# v0_2_0.net
KiCad netlist of a schematic drawn in EAGLE
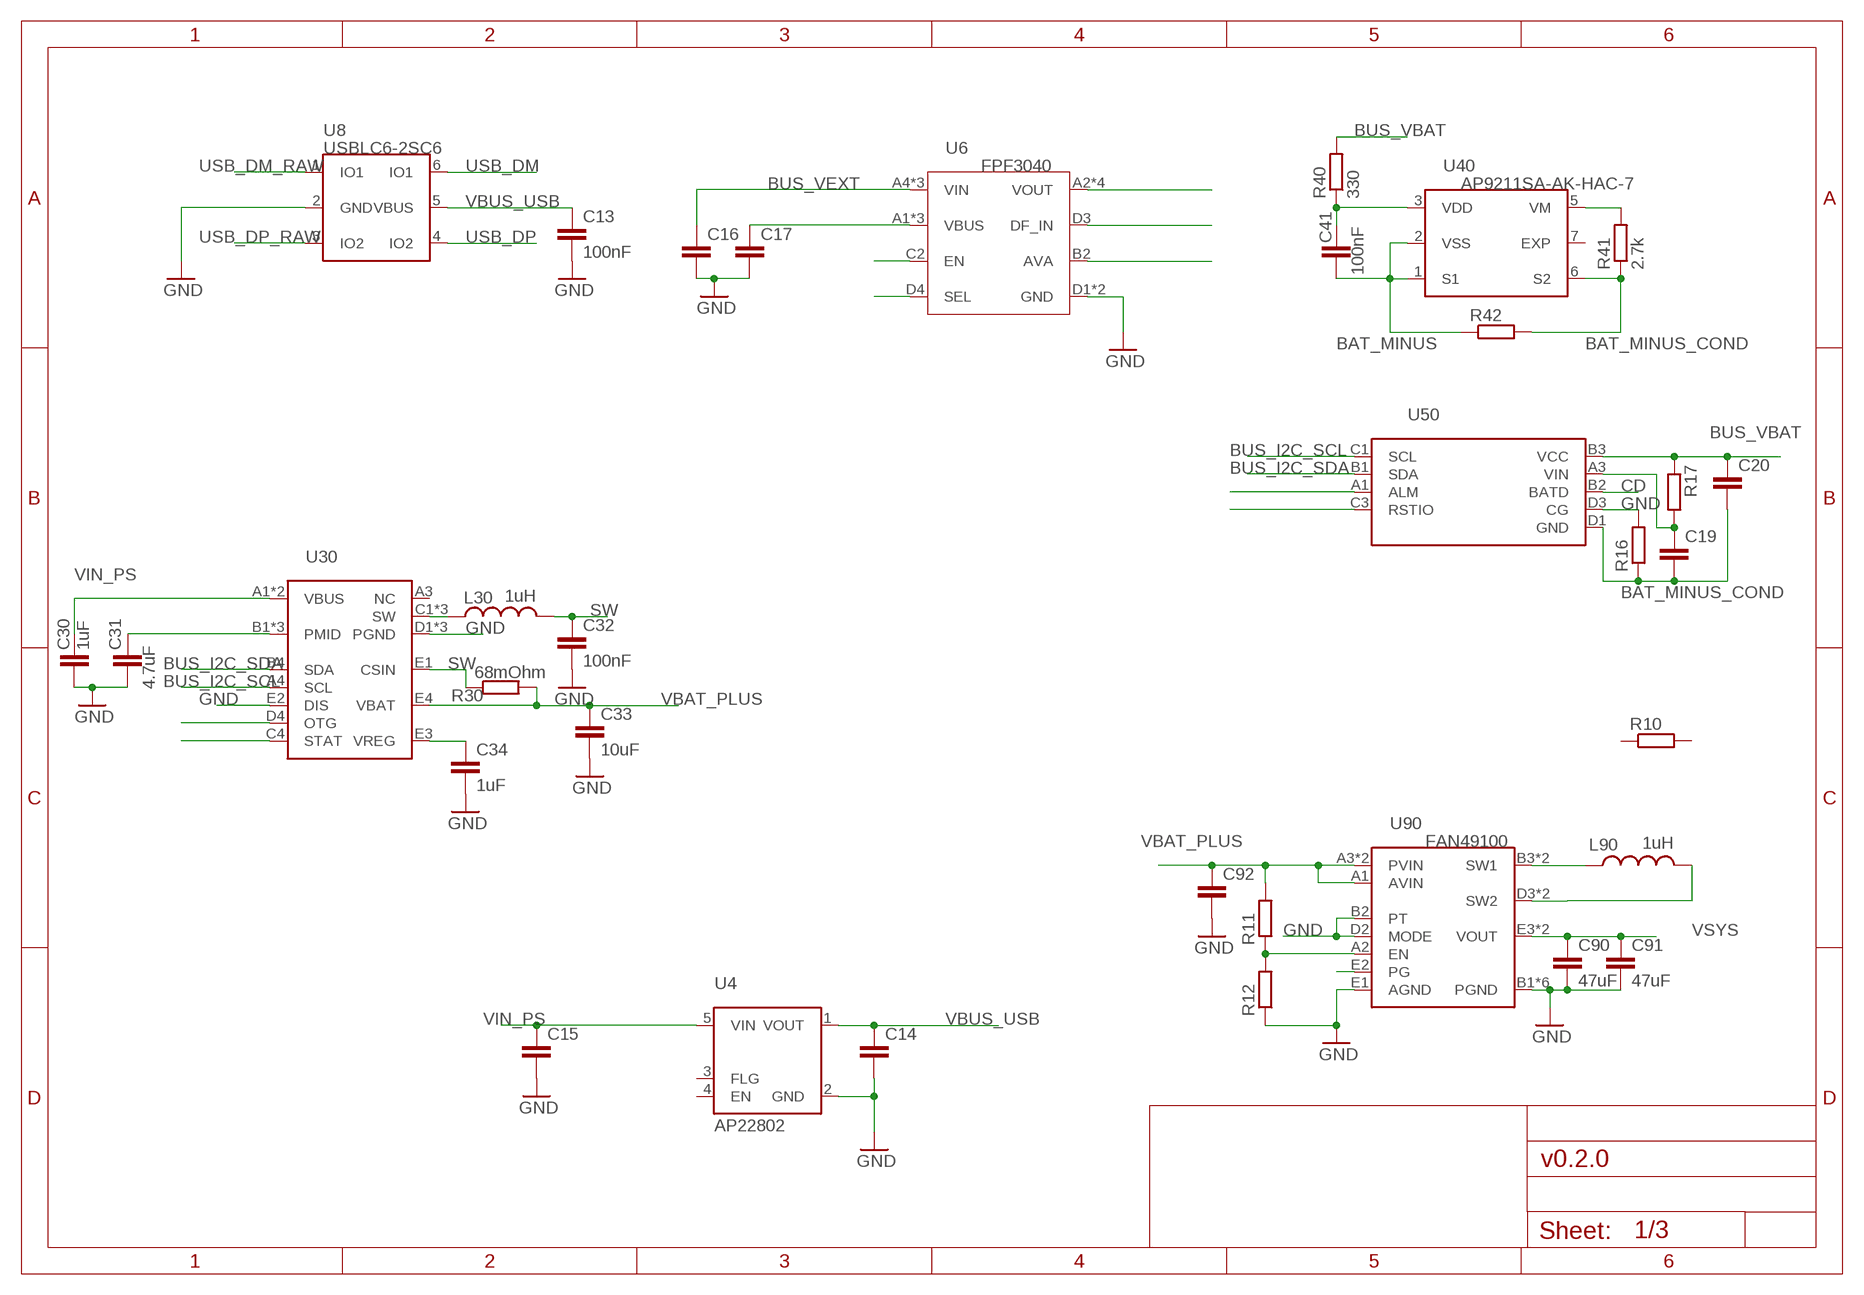
[diagram p0: schematic, sheet 1]
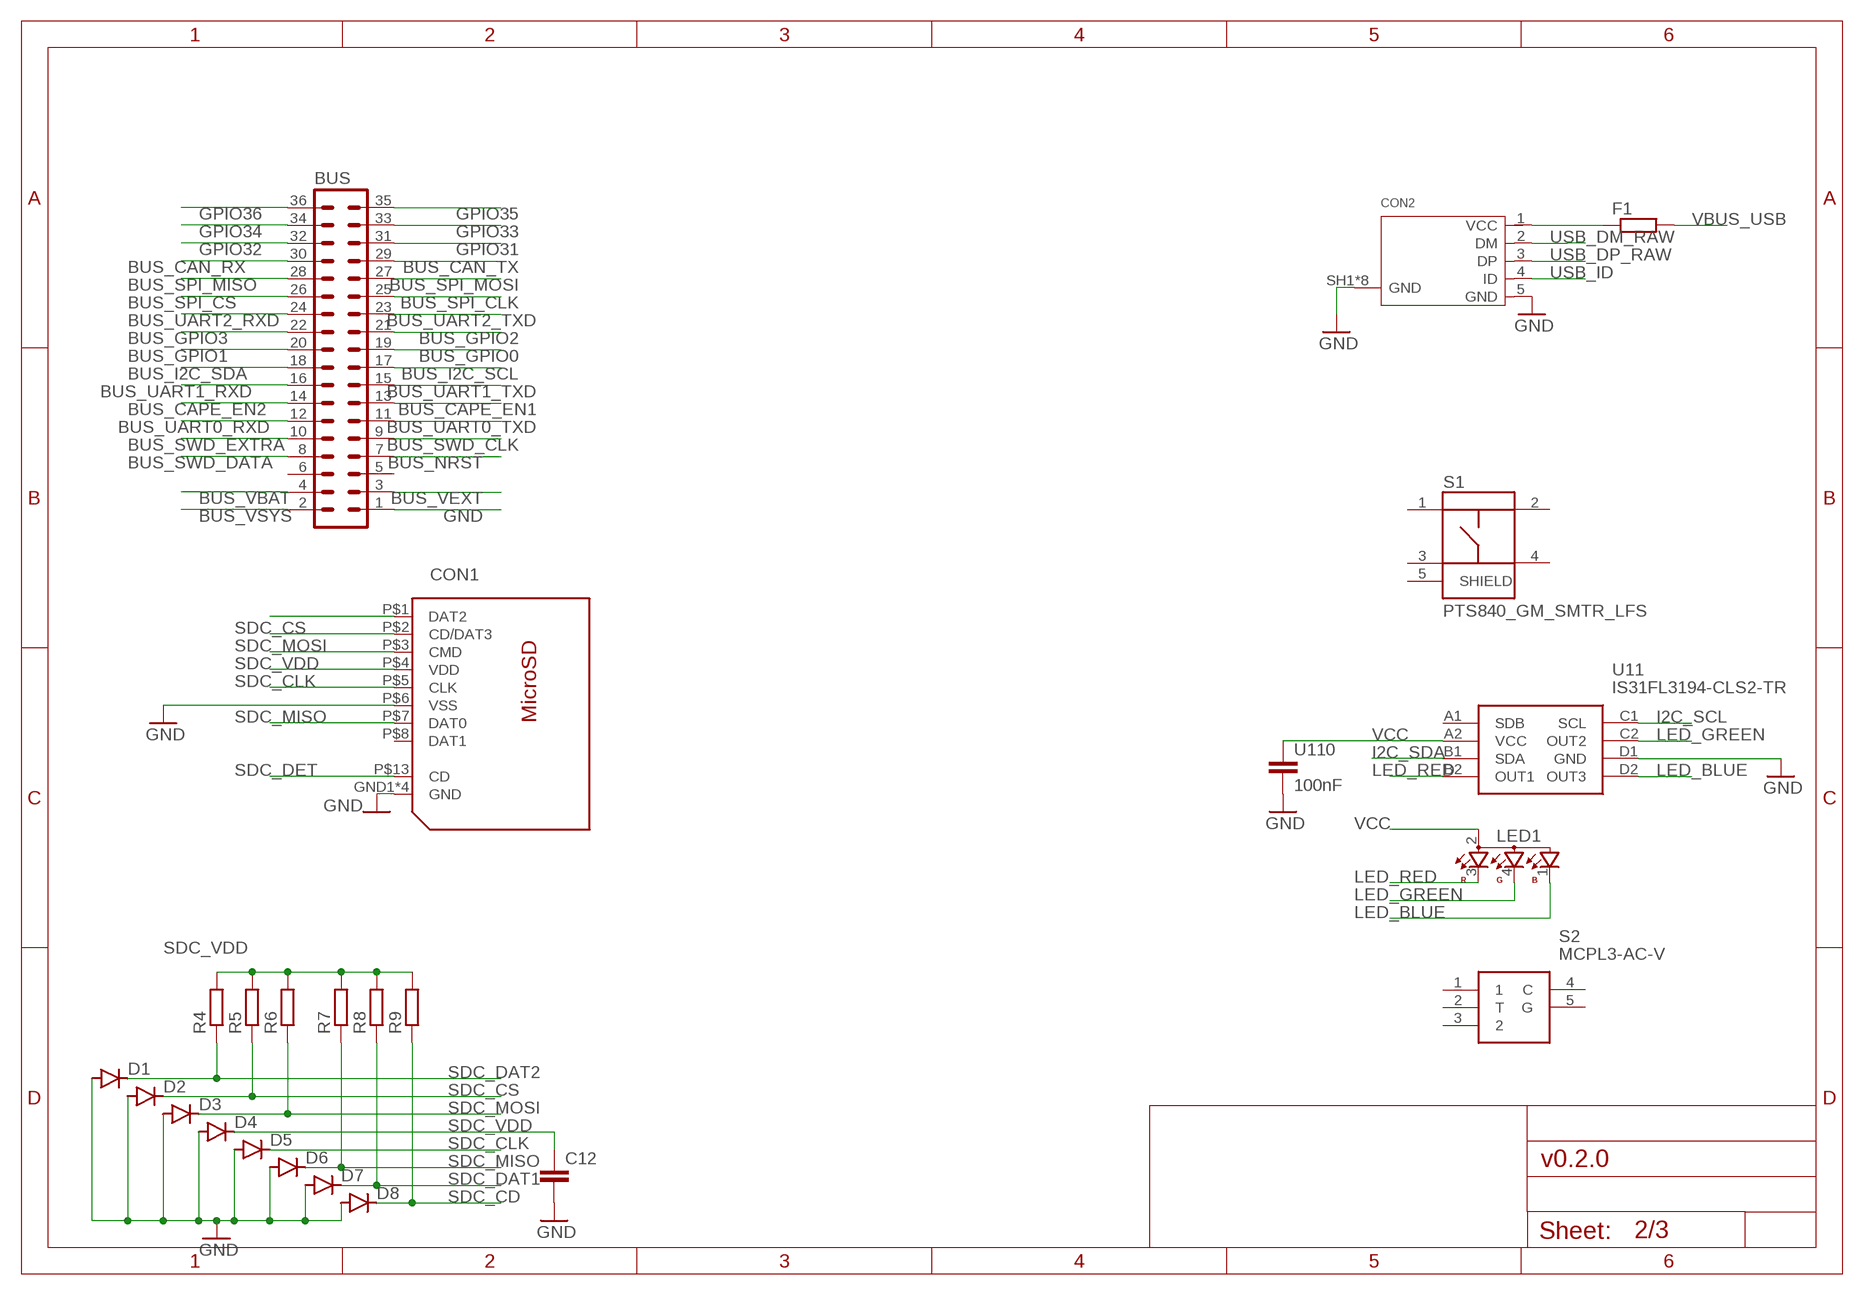
[diagram p1: schematic, sheet 2]
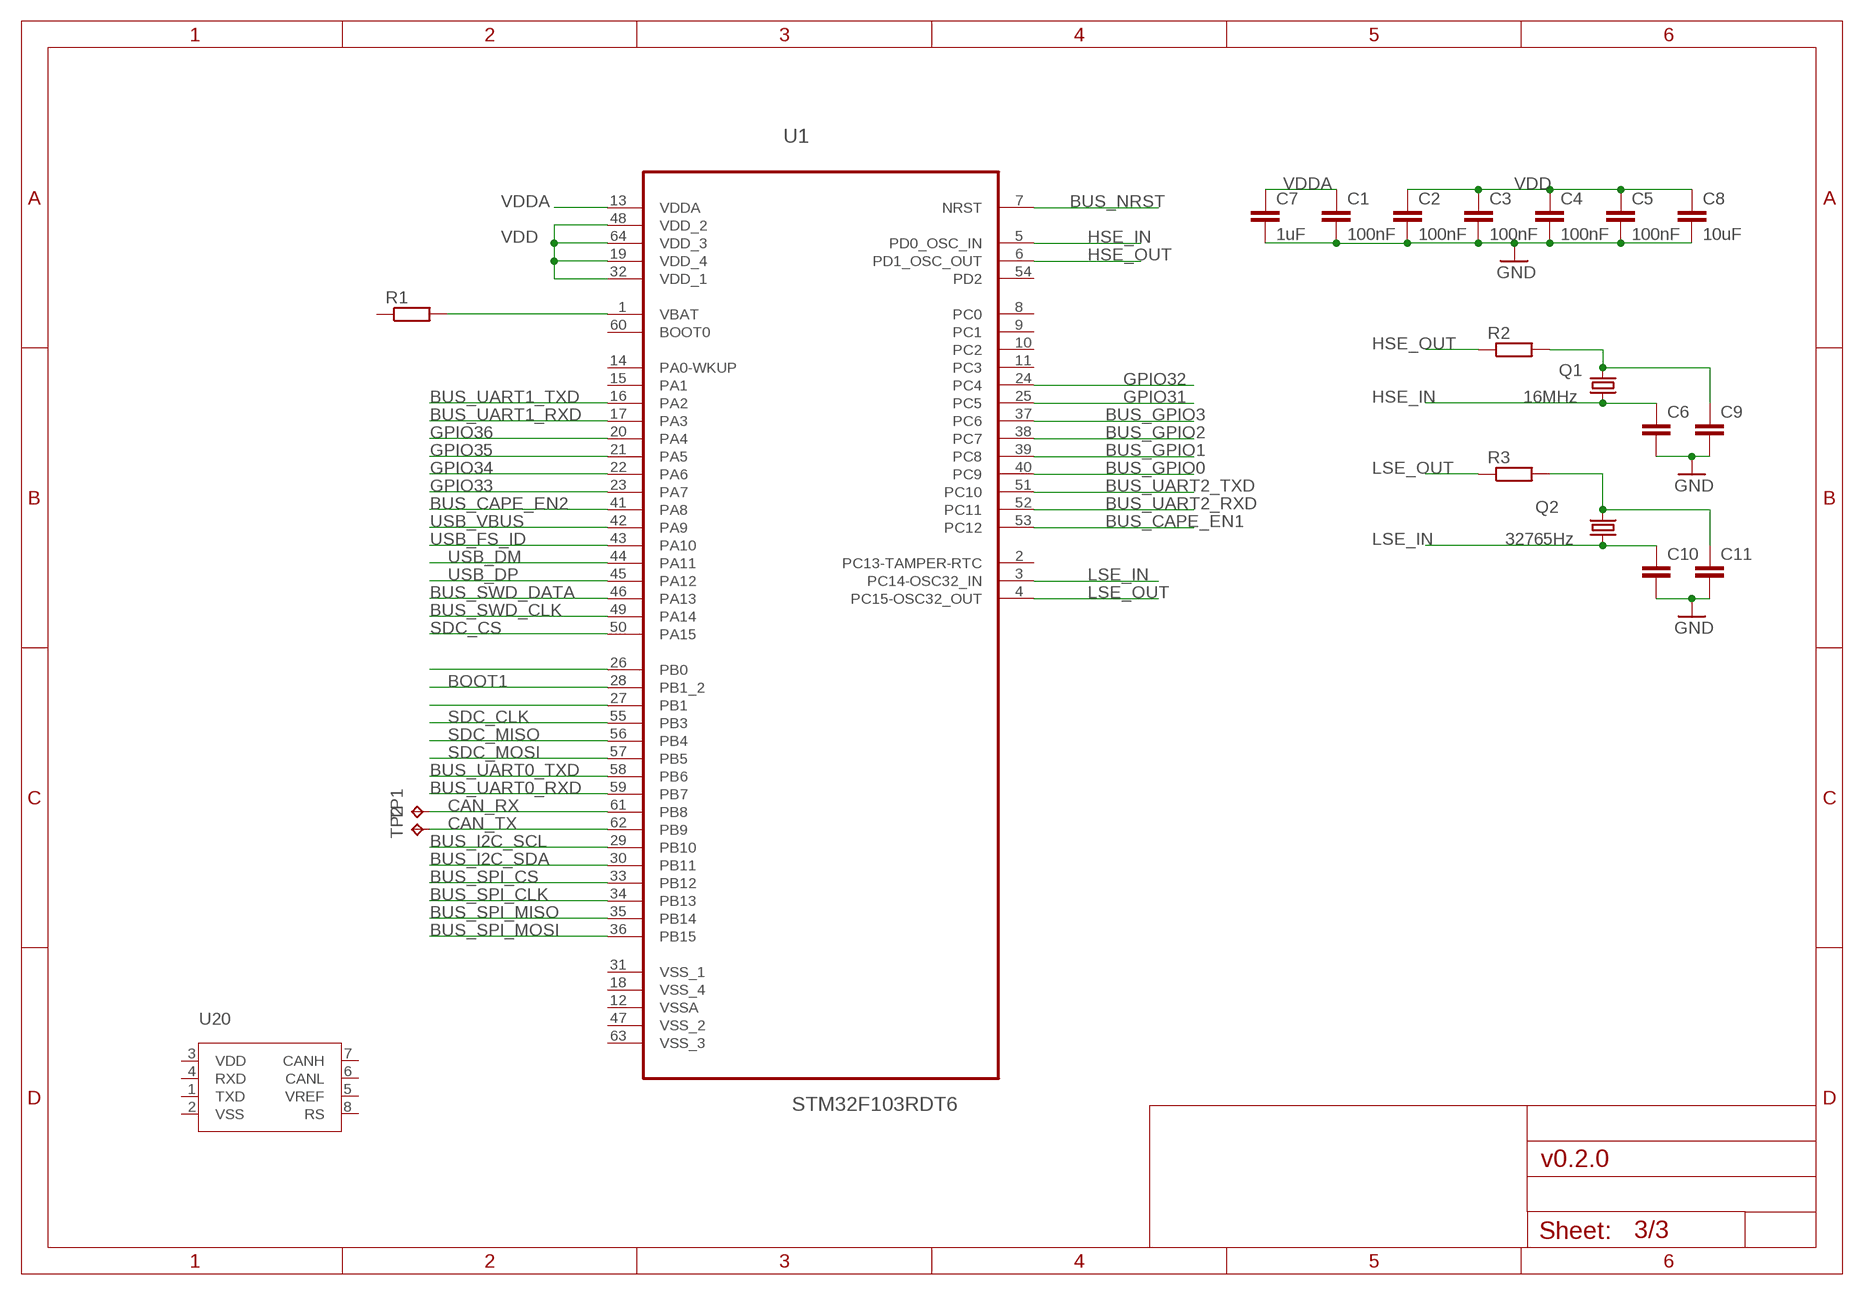
[diagram p2: schematic, sheet 3]

(export (version "E")
  (design (tool "Eeschema 10.0.6"))
  (components
    (comp (ref "C13")
      (value "100nF")
      (footprint "eagle-import:C0402")
      (libsource (lib "eagle-import") (part "C-EUC0402"))
    )
    (comp (ref "C14")
      (value "C-EUC0603")
      (footprint "eagle-import:C0603")
      (libsource (lib "eagle-import") (part "C-EUC0603"))
    )
    (comp (ref "C15")
      (value "C-EUC0603")
      (footprint "eagle-import:C0603")
      (libsource (lib "eagle-import") (part "C-EUC0603"))
    )
    (comp (ref "C16")
      (value "C-EUC0603")
      (footprint "eagle-import:C0603")
      (libsource (lib "eagle-import") (part "C-EUC0603"))
    )
    (comp (ref "C17")
      (value "C-EUC0603")
      (footprint "eagle-import:C0603")
      (libsource (lib "eagle-import") (part "C-EUC0603"))
    )
    (comp (ref "C19")
      (value "C-EUC0402")
      (footprint "eagle-import:C0402")
      (libsource (lib "eagle-import") (part "C-EUC0402"))
    )
    (comp (ref "C20")
      (value "C-EUC0402")
      (footprint "eagle-import:C0402")
      (libsource (lib "eagle-import") (part "C-EUC0402"))
    )
    (comp (ref "C30")
      (value "1uF")
      (footprint "eagle-import:C0402")
      (libsource (lib "eagle-import") (part "C-EUC0402"))
    )
    (comp (ref "C31")
      (value "4.7uF")
      (footprint "eagle-import:C0603")
      (libsource (lib "eagle-import") (part "C-EUC0603"))
    )
    (comp (ref "C32")
      (value "100nF")
      (footprint "eagle-import:C0402")
      (libsource (lib "eagle-import") (part "C-EUC0402"))
    )
    (comp (ref "C33")
      (value "10uF")
      (footprint "eagle-import:C0603")
      (libsource (lib "eagle-import") (part "C-EUC0603"))
    )
    (comp (ref "C34")
      (value "1uF")
      (footprint "eagle-import:C0402")
      (libsource (lib "eagle-import") (part "C-EUC0402"))
    )
    (comp (ref "C41")
      (value "100nF")
      (footprint "eagle-import:C0402")
      (libsource (lib "eagle-import") (part "C-EUC0402"))
    )
    (comp (ref "C90")
      (value "47uF")
      (footprint "eagle-import:C0805")
      (libsource (lib "eagle-import") (part "C-EUC0805"))
    )
    (comp (ref "C91")
      (value "47uF")
      (footprint "eagle-import:C0805")
      (libsource (lib "eagle-import") (part "C-EUC0805"))
    )
    (comp (ref "C92")
      (value "C-EUC0805")
      (footprint "eagle-import:C0805")
      (libsource (lib "eagle-import") (part "C-EUC0805"))
    )
    (comp (ref "L30")
      (value "1uH")
      (footprint "eagle-import:L3230M")
      (libsource (lib "eagle-import") (part "DJNR3015"))
    )
    (comp (ref "L90")
      (value "1uH")
      (footprint "eagle-import:L3230M")
      (libsource (lib "eagle-import") (part "DJNR3015"))
    )
    (comp (ref "R10")
      (value "R-EU_R0603")
      (footprint "eagle-import:R0603")
      (libsource (lib "eagle-import") (part "R-EU_R0603"))
    )
    (comp (ref "R11")
      (value "R-EU_R0402")
      (footprint "eagle-import:R0402")
      (libsource (lib "eagle-import") (part "R-EU_R0402"))
    )
    (comp (ref "R12")
      (value "R-EU_R0402")
      (footprint "eagle-import:R0402")
      (libsource (lib "eagle-import") (part "R-EU_R0402"))
    )
    (comp (ref "R16")
      (value "R-EU_R0805")
      (footprint "eagle-import:R0805")
      (libsource (lib "eagle-import") (part "R-EU_R0805"))
    )
    (comp (ref "R17")
      (value "R-EU_R0402")
      (footprint "eagle-import:R0402")
      (libsource (lib "eagle-import") (part "R-EU_R0402"))
    )
    (comp (ref "R30")
      (value "68mOhm")
      (footprint "eagle-import:R0805")
      (libsource (lib "eagle-import") (part "R-EU_R0805"))
    )
    (comp (ref "R40")
      (value "330")
      (footprint "eagle-import:R0402")
      (libsource (lib "eagle-import") (part "R-EU_R0402"))
    )
    (comp (ref "R41")
      (value "2.7k")
      (footprint "eagle-import:R0402")
      (libsource (lib "eagle-import") (part "R-EU_R0402"))
    )
    (comp (ref "R42")
      (value "R-EU_R0603")
      (footprint "eagle-import:R0603")
      (libsource (lib "eagle-import") (part "R-EU_R0603"))
    )
    (comp (ref "U4")
      (value "AP22802")
      (footprint "eagle-import:SOT25")
      (libsource (lib "eagle-import") (part "AP22802"))
    )
    (comp (ref "U6")
      (value "FPF3040")
      (footprint "eagle-import:BGA16C40P4X4_196X176X60")
      (libsource (lib "eagle-import") (part "FPF3040"))
    )
    (comp (ref "U8")
      (value "USBLC6-2SC6")
      (footprint "eagle-import:SOT95P280X110-6")
      (libsource (lib "eagle-import") (part "USBLC6-2SC6"))
    )
    (comp (ref "U30")
      (value "FAN54015")
      (footprint "eagle-import:BGA20C40P4X5_196X187X55")
      (libsource (lib "eagle-import") (part "FAN54015"))
    )
    (comp (ref "U40")
      (value "AP9211SA-AK-HAC-7")
      (footprint "eagle-import:DFN200X300X60-7N")
      (fields (field (name "MF") "Diodes Inc."))
      (libsource (lib "eagle-import") (part "AP9211SA-AK-HAC-7"))
    )
    (comp (ref "U50")
      (value "STC3115")
      (footprint "eagle-import:BGA12C40P4X3_137X201X65")
      (libsource (lib "eagle-import") (part "STC3115"))
    )
    (comp (ref "U90")
      (value "FAN49100")
      (footprint "eagle-import:BGA20C40P4X5_201X161X60")
      (libsource (lib "eagle-import") (part "FAN49100"))
    )
    (comp (ref "C1")
      (value "100nF")
      (footprint "eagle-import:C0402")
      (libsource (lib "eagle-import") (part "C-EUC0402"))
    )
    (comp (ref "C2")
      (value "100nF")
      (footprint "eagle-import:C0402")
      (libsource (lib "eagle-import") (part "C-EUC0402"))
    )
    (comp (ref "C3")
      (value "100nF")
      (footprint "eagle-import:C0402")
      (libsource (lib "eagle-import") (part "C-EUC0402"))
    )
    (comp (ref "C4")
      (value "100nF")
      (footprint "eagle-import:C0402")
      (libsource (lib "eagle-import") (part "C-EUC0402"))
    )
    (comp (ref "C5")
      (value "100nF")
      (footprint "eagle-import:C0402")
      (libsource (lib "eagle-import") (part "C-EUC0402"))
    )
    (comp (ref "C6")
      (value "C-EUC0402")
      (footprint "eagle-import:C0402")
      (libsource (lib "eagle-import") (part "C-EUC0402"))
    )
    (comp (ref "C7")
      (value "1uF")
      (footprint "eagle-import:C0402")
      (libsource (lib "eagle-import") (part "C-EUC0402"))
    )
    (comp (ref "C8")
      (value "10uF")
      (footprint "eagle-import:C0603")
      (libsource (lib "eagle-import") (part "C-EUC0603"))
    )
    (comp (ref "C9")
      (value "C-EUC0402")
      (footprint "eagle-import:C0402")
      (libsource (lib "eagle-import") (part "C-EUC0402"))
    )
    (comp (ref "C10")
      (value "C-EUC0402")
      (footprint "eagle-import:C0402")
      (libsource (lib "eagle-import") (part "C-EUC0402"))
    )
    (comp (ref "C11")
      (value "C-EUC0402")
      (footprint "eagle-import:C0402")
      (libsource (lib "eagle-import") (part "C-EUC0402"))
    )
    (comp (ref "Q1")
      (value "16MHz")
      (footprint "eagle-import:3.2X2.5_KX-7")
      (libsource (lib "eagle-import") (part "KX-7"))
    )
    (comp (ref "Q2")
      (value "32765Hz")
      (footprint "eagle-import:3.2X1.5")
      (libsource (lib "eagle-import") (part "KX-327-NHF"))
    )
    (comp (ref "R1")
      (value "R-EU_R0402")
      (footprint "eagle-import:R0402")
      (libsource (lib "eagle-import") (part "R-EU_R0402"))
    )
    (comp (ref "R2")
      (value "R-EU_R0402")
      (footprint "eagle-import:R0402")
      (libsource (lib "eagle-import") (part "R-EU_R0402"))
    )
    (comp (ref "R3")
      (value "R-EU_R0402")
      (footprint "eagle-import:R0402")
      (libsource (lib "eagle-import") (part "R-EU_R0402"))
    )
    (comp (ref "TP1")
      (value "TPB1,27")
      (footprint "eagle-import:B1,27")
      (libsource (lib "eagle-import") (part "TPB1,27"))
    )
    (comp (ref "TP2")
      (value "TPB1,27")
      (footprint "eagle-import:B1,27")
      (libsource (lib "eagle-import") (part "TPB1,27"))
    )
    (comp (ref "U1")
      (value "STM32F103RDT6")
      (footprint "eagle-import:QFP50P1200X1200X160-64N")
      (fields (field (name "MF") "STMicroelectronics"))
      (libsource (lib "eagle-import") (part "STM32F103RDT6"))
    )
    (comp (ref "U20")
      (value "MCP2551")
      (footprint "eagle-import:SOIC8")
      (libsource (lib "eagle-import") (part "MCP2551"))
    )
    (comp (ref "BUS")
      (value "MA18-2")
      (footprint "eagle-import:MA18-2")
      (libsource (lib "eagle-import") (part "MA18-2"))
    )
    (comp (ref "C12")
      (value "C-EUC0402")
      (footprint "eagle-import:C0402")
      (libsource (lib "eagle-import") (part "C-EUC0402"))
    )
    (comp (ref "CON1")
      (value "112J-TXAR")
      (footprint "eagle-import:112J")
      (libsource (lib "eagle-import") (part "112J-TXAR"))
    )
    (comp (ref "CON2")
      (value "10118194-0001LF")
      (footprint "eagle-import:10118194")
      (libsource (lib "eagle-import") (part "10118194-0001LF"))
    )
    (comp (ref "D1")
      (value "DIODE-SOD523")
      (footprint "eagle-import:SOD523")
      (libsource (lib "eagle-import") (part "DIODE-SOD523"))
    )
    (comp (ref "D2")
      (value "DIODE-SOD523")
      (footprint "eagle-import:SOD523")
      (libsource (lib "eagle-import") (part "DIODE-SOD523"))
    )
    (comp (ref "D3")
      (value "DIODE-SOD523")
      (footprint "eagle-import:SOD523")
      (libsource (lib "eagle-import") (part "DIODE-SOD523"))
    )
    (comp (ref "D4")
      (value "DIODE-SOD523")
      (footprint "eagle-import:SOD523")
      (libsource (lib "eagle-import") (part "DIODE-SOD523"))
    )
    (comp (ref "D5")
      (value "DIODE-SOD523")
      (footprint "eagle-import:SOD523")
      (libsource (lib "eagle-import") (part "DIODE-SOD523"))
    )
    (comp (ref "D6")
      (value "DIODE-SOD523")
      (footprint "eagle-import:SOD523")
      (libsource (lib "eagle-import") (part "DIODE-SOD523"))
    )
    (comp (ref "D7")
      (value "DIODE-SOD523")
      (footprint "eagle-import:SOD523")
      (libsource (lib "eagle-import") (part "DIODE-SOD523"))
    )
    (comp (ref "D8")
      (value "DIODE-SOD523")
      (footprint "eagle-import:SOD523")
      (libsource (lib "eagle-import") (part "DIODE-SOD523"))
    )
    (comp (ref "F1")
      (value "R-EU_R0603")
      (footprint "eagle-import:R0603")
      (libsource (lib "eagle-import") (part "R-EU_R0603"))
    )
    (comp (ref "LED1")
      (value "OSTB1204C1E")
      (footprint "eagle-import:321015RGB")
      (libsource (lib "eagle-import") (part "OSTB1204C1E"))
    )
    (comp (ref "R4")
      (value "R-EU_R0402")
      (footprint "eagle-import:R0402")
      (libsource (lib "eagle-import") (part "R-EU_R0402"))
    )
    (comp (ref "R5")
      (value "R-EU_R0402")
      (footprint "eagle-import:R0402")
      (libsource (lib "eagle-import") (part "R-EU_R0402"))
    )
    (comp (ref "R6")
      (value "R-EU_R0402")
      (footprint "eagle-import:R0402")
      (libsource (lib "eagle-import") (part "R-EU_R0402"))
    )
    (comp (ref "R7")
      (value "R-EU_R0402")
      (footprint "eagle-import:R0402")
      (libsource (lib "eagle-import") (part "R-EU_R0402"))
    )
    (comp (ref "R8")
      (value "R-EU_R0402")
      (footprint "eagle-import:R0402")
      (libsource (lib "eagle-import") (part "R-EU_R0402"))
    )
    (comp (ref "R9")
      (value "R-EU_R0402")
      (footprint "eagle-import:R0402")
      (libsource (lib "eagle-import") (part "R-EU_R0402"))
    )
    (comp (ref "S1")
      (value "PTS840_GM_SMTR_LFS")
      (footprint "eagle-import:SW_PTS840GMSMTRLFS")
      (fields (field (name "MF") "C&K") (field (name "MP") "PTS840 GM SMTR LFS"))
      (libsource (lib "eagle-import") (part "PTS840_GM_SMTR_LFS"))
    )
    (comp (ref "S2")
      (value "MCPL3-AC-V")
      (footprint "eagle-import:MCPL3-AC-V")
      (libsource (lib "eagle-import") (part "MCPL3-AC-V"))
    )
    (comp (ref "U11")
      (value "IS31FL3194-CLS2-TR")
      (footprint "eagle-import:BGA8C40P2X4_99X159X42")
      (fields (field (name "MOUSER_PART_NUMBER") "870-IS31FL3194CLS2TR"))
      (libsource (lib "eagle-import") (part "IS31FL3194-CLS2-TR"))
    )
    (comp (ref "U110")
      (value "100nF")
      (footprint "eagle-import:C0402")
      (libsource (lib "eagle-import") (part "C-EUC0402"))
    )
  )
  (nets
    (net (code "1") (name "BAT_MINUS") (class "Default")
      (node (ref "C41") (pin "2") (pinfunction "2_2") (pintype "passive"))
      (node (ref "R42") (pin "1") (pinfunction "1_1") (pintype "passive"))
      (node (ref "U40") (pin "1") (pinfunction "S1_1") (pintype "output"))
      (node (ref "U40") (pin "2") (pinfunction "VSS_2") (pintype "power_in"))
    )
    (net (code "2") (name "BAT_MINUS_COND") (class "Default")
      (node (ref "C19") (pin "2") (pinfunction "2_2") (pintype "passive"))
      (node (ref "C20") (pin "2") (pinfunction "2_2") (pintype "passive"))
      (node (ref "R16") (pin "1") (pinfunction "1_1") (pintype "passive"))
      (node (ref "R41") (pin "1") (pinfunction "1_1") (pintype "passive"))
      (node (ref "R42") (pin "2") (pinfunction "2_2") (pintype "passive"))
      (node (ref "U40") (pin "6") (pinfunction "S2_6") (pintype "output"))
      (node (ref "U50") (pin "D1") (pinfunction "GND_D1") (pintype "bidirectional"))
    )
    (net (code "3") (name "BOOT1") (class "Default")
      (node (ref "U1") (pin "28") (pinfunction "PB1_2_28") (pintype "bidirectional"))
    )
    (net (code "4") (name "BUS_CAN_RX") (class "Default")
      (node (ref "BUS") (pin "30") (pinfunction "30_30") (pintype "passive"))
    )
    (net (code "5") (name "BUS_CAN_TX") (class "Default")
      (node (ref "BUS") (pin "29") (pinfunction "29_29") (pintype "passive"))
    )
    (net (code "6") (name "BUS_CAPE_EN1") (class "Default")
      (node (ref "BUS") (pin "13") (pinfunction "13_13") (pintype "passive"))
      (node (ref "U1") (pin "53") (pinfunction "PC12_53") (pintype "bidirectional"))
    )
    (net (code "7") (name "BUS_CAPE_EN2") (class "Default")
      (node (ref "BUS") (pin "14") (pinfunction "14_14") (pintype "passive"))
      (node (ref "U1") (pin "41") (pinfunction "PA8_41") (pintype "bidirectional"))
    )
    (net (code "8") (name "BUS_GPIO0") (class "Default")
      (node (ref "BUS") (pin "19") (pinfunction "19_19") (pintype "passive"))
      (node (ref "U1") (pin "40") (pinfunction "PC9_40") (pintype "bidirectional"))
    )
    (net (code "9") (name "BUS_GPIO1") (class "Default")
      (node (ref "BUS") (pin "20") (pinfunction "20_20") (pintype "passive"))
      (node (ref "U1") (pin "39") (pinfunction "PC8_39") (pintype "bidirectional"))
    )
    (net (code "10") (name "BUS_GPIO2") (class "Default")
      (node (ref "BUS") (pin "21") (pinfunction "21_21") (pintype "passive"))
      (node (ref "U1") (pin "38") (pinfunction "PC7_38") (pintype "bidirectional"))
    )
    (net (code "11") (name "BUS_GPIO3") (class "Default")
      (node (ref "BUS") (pin "22") (pinfunction "22_22") (pintype "passive"))
      (node (ref "U1") (pin "37") (pinfunction "PC6_37") (pintype "bidirectional"))
    )
    (net (code "12") (name "BUS_I2C_SCL") (class "Default")
      (node (ref "BUS") (pin "17") (pinfunction "17_17") (pintype "passive"))
      (node (ref "U1") (pin "29") (pinfunction "PB10_29") (pintype "bidirectional"))
      (node (ref "U30") (pin "A4") (pinfunction "SCL_A4") (pintype "bidirectional"))
      (node (ref "U50") (pin "C1") (pinfunction "SCL_C1") (pintype "bidirectional"))
    )
    (net (code "13") (name "BUS_I2C_SDA") (class "Default")
      (node (ref "BUS") (pin "18") (pinfunction "18_18") (pintype "passive"))
      (node (ref "U1") (pin "30") (pinfunction "PB11_30") (pintype "bidirectional"))
      (node (ref "U30") (pin "B4") (pinfunction "SDA_B4") (pintype "bidirectional"))
      (node (ref "U50") (pin "B1") (pinfunction "SDA_B1") (pintype "bidirectional"))
    )
    (net (code "14") (name "BUS_NRST") (class "Default")
      (node (ref "BUS") (pin "7") (pinfunction "7_7") (pintype "passive"))
      (node (ref "U1") (pin "7") (pinfunction "NRST_7") (pintype "output"))
    )
    (net (code "15") (name "BUS_SPI_CLK") (class "Default")
      (node (ref "BUS") (pin "25") (pinfunction "25_25") (pintype "passive"))
      (node (ref "U1") (pin "34") (pinfunction "PB13_34") (pintype "bidirectional"))
    )
    (net (code "16") (name "BUS_SPI_CS") (class "Default")
      (node (ref "BUS") (pin "26") (pinfunction "26_26") (pintype "passive"))
      (node (ref "U1") (pin "33") (pinfunction "PB12_33") (pintype "bidirectional"))
    )
    (net (code "17") (name "BUS_SPI_MISO") (class "Default")
      (node (ref "BUS") (pin "28") (pinfunction "28_28") (pintype "passive"))
      (node (ref "U1") (pin "35") (pinfunction "PB14_35") (pintype "bidirectional"))
    )
    (net (code "18") (name "BUS_SPI_MOSI") (class "Default")
      (node (ref "BUS") (pin "27") (pinfunction "27_27") (pintype "passive"))
      (node (ref "U1") (pin "36") (pinfunction "PB15_36") (pintype "bidirectional"))
    )
    (net (code "19") (name "BUS_SWD_CLK") (class "Default")
      (node (ref "BUS") (pin "9") (pinfunction "9_9") (pintype "passive"))
      (node (ref "U1") (pin "49") (pinfunction "PA14_49") (pintype "bidirectional"))
    )
    (net (code "20") (name "BUS_SWD_DATA") (class "Default")
      (node (ref "BUS") (pin "8") (pinfunction "8_8") (pintype "passive"))
      (node (ref "U1") (pin "46") (pinfunction "PA13_46") (pintype "bidirectional"))
    )
    (net (code "21") (name "BUS_SWD_EXTRA") (class "Default")
      (node (ref "BUS") (pin "10") (pinfunction "10_10") (pintype "passive"))
    )
    (net (code "22") (name "BUS_UART0_RXD") (class "Default")
      (node (ref "BUS") (pin "12") (pinfunction "12_12") (pintype "passive"))
      (node (ref "U1") (pin "59") (pinfunction "PB7_59") (pintype "power_in"))
    )
    (net (code "23") (name "BUS_UART0_TXD") (class "Default")
      (node (ref "BUS") (pin "11") (pinfunction "11_11") (pintype "passive"))
      (node (ref "U1") (pin "58") (pinfunction "PB6_58") (pintype "bidirectional"))
    )
    (net (code "24") (name "BUS_UART1_RXD") (class "Default")
      (node (ref "BUS") (pin "16") (pinfunction "16_16") (pintype "passive"))
      (node (ref "U1") (pin "17") (pinfunction "PA3_17") (pintype "bidirectional"))
    )
    (net (code "25") (name "BUS_UART1_TXD") (class "Default")
      (node (ref "BUS") (pin "15") (pinfunction "15_15") (pintype "passive"))
      (node (ref "U1") (pin "16") (pinfunction "PA2_16") (pintype "bidirectional"))
    )
    (net (code "26") (name "BUS_UART2_RXD") (class "Default")
      (node (ref "BUS") (pin "24") (pinfunction "24_24") (pintype "passive"))
      (node (ref "U1") (pin "52") (pinfunction "PC11_52") (pintype "bidirectional"))
    )
    (net (code "27") (name "BUS_UART2_TXD") (class "Default")
      (node (ref "BUS") (pin "23") (pinfunction "23_23") (pintype "passive"))
      (node (ref "U1") (pin "51") (pinfunction "PC10_51") (pintype "bidirectional"))
    )
    (net (code "28") (name "BUS_VBAT") (class "Default")
      (node (ref "BUS") (pin "4") (pinfunction "4_4") (pintype "passive"))
      (node (ref "C20") (pin "1") (pinfunction "1_1") (pintype "passive"))
      (node (ref "R17") (pin "1") (pinfunction "1_1") (pintype "passive"))
      (node (ref "R40") (pin "2") (pinfunction "2_2") (pintype "passive"))
      (node (ref "U50") (pin "B3") (pinfunction "VCC_B3") (pintype "bidirectional"))
    )
    (net (code "29") (name "BUS_VEXT") (class "Default")
      (node (ref "BUS") (pin "3") (pinfunction "3_3") (pintype "passive"))
      (node (ref "C16") (pin "1") (pinfunction "1_1") (pintype "passive"))
      (node (ref "U6") (pin "A4") (pinfunction "VIN_A4") (pintype "bidirectional"))
      (node (ref "U6") (pin "B4") (pinfunction "VIN_B4") (pintype "bidirectional"))
      (node (ref "U6") (pin "C4") (pinfunction "VIN_C4") (pintype "bidirectional"))
    )
    (net (code "30") (name "BUS_VSYS") (class "Default")
      (node (ref "BUS") (pin "2") (pinfunction "2_2") (pintype "passive"))
    )
    (net (code "31") (name "CAN_RX") (class "Default")
      (node (ref "TP1") (pin "TP") (pinfunction "TP_TP") (pintype "input"))
      (node (ref "U1") (pin "61") (pinfunction "PB8_61") (pintype "bidirectional"))
    )
    (net (code "32") (name "CAN_TX") (class "Default")
      (node (ref "TP2") (pin "TP") (pinfunction "TP_TP") (pintype "input"))
      (node (ref "U1") (pin "62") (pinfunction "PB9_62") (pintype "bidirectional"))
    )
    (net (code "33") (name "CD") (class "Default")
      (node (ref "U50") (pin "B2") (pinfunction "BATD_B2") (pintype "bidirectional"))
    )
    (net (code "34") (name "DAT1") (class "Default")
      (node (ref "CON1") (pin "P$8") (pinfunction "DAT1_P$8") (pintype "power_in"))
    )
    (net (code "35") (name "EXP") (class "Default")
      (node (ref "U40") (pin "7") (pinfunction "EXP_7") (pintype "power_in"))
    )
    (net (code "36") (name "GND") (class "Default")
      (node (ref "BUS") (pin "1") (pinfunction "1_1") (pintype "passive"))
      (node (ref "C1") (pin "2") (pinfunction "2_2") (pintype "passive"))
      (node (ref "C10") (pin "2") (pinfunction "2_2") (pintype "passive"))
      (node (ref "C11") (pin "2") (pinfunction "2_2") (pintype "passive"))
      (node (ref "C12") (pin "2") (pinfunction "2_2") (pintype "passive"))
      (node (ref "C13") (pin "2") (pinfunction "2_2") (pintype "passive"))
      (node (ref "C14") (pin "2") (pinfunction "2_2") (pintype "passive"))
      (node (ref "C15") (pin "2") (pinfunction "2_2") (pintype "passive"))
      (node (ref "C16") (pin "2") (pinfunction "2_2") (pintype "passive"))
      (node (ref "C17") (pin "2") (pinfunction "2_2") (pintype "passive"))
      (node (ref "C2") (pin "2") (pinfunction "2_2") (pintype "passive"))
      (node (ref "C3") (pin "2") (pinfunction "2_2") (pintype "passive"))
      (node (ref "C30") (pin "2") (pinfunction "2_2") (pintype "passive"))
      (node (ref "C31") (pin "2") (pinfunction "2_2") (pintype "passive"))
      (node (ref "C32") (pin "2") (pinfunction "2_2") (pintype "passive"))
      (node (ref "C33") (pin "2") (pinfunction "2_2") (pintype "passive"))
      (node (ref "C34") (pin "2") (pinfunction "2_2") (pintype "passive"))
      (node (ref "C4") (pin "2") (pinfunction "2_2") (pintype "passive"))
      (node (ref "C5") (pin "2") (pinfunction "2_2") (pintype "passive"))
      (node (ref "C6") (pin "2") (pinfunction "2_2") (pintype "passive"))
      (node (ref "C7") (pin "2") (pinfunction "2_2") (pintype "passive"))
      (node (ref "C8") (pin "2") (pinfunction "2_2") (pintype "passive"))
      (node (ref "C9") (pin "2") (pinfunction "2_2") (pintype "passive"))
      (node (ref "C90") (pin "2") (pinfunction "2_2") (pintype "passive"))
      (node (ref "C91") (pin "2") (pinfunction "2_2") (pintype "passive"))
      (node (ref "C92") (pin "2") (pinfunction "2_2") (pintype "passive"))
      (node (ref "CON1") (pin "GND1") (pinfunction "GND_GND1") (pintype "power_in"))
      (node (ref "CON1") (pin "GND2") (pinfunction "GND_GND2") (pintype "power_in"))
      (node (ref "CON1") (pin "GND3") (pinfunction "GND_GND3") (pintype "power_in"))
      (node (ref "CON1") (pin "GND4") (pinfunction "GND_GND4") (pintype "power_in"))
      (node (ref "CON1") (pin "P$6") (pinfunction "VSS_P$6") (pintype "bidirectional"))
      (node (ref "CON2") (pin "5") (pinfunction "GND_5") (pintype "bidirectional"))
      (node (ref "CON2") (pin "SH1") (pinfunction "GND_SH1") (pintype "bidirectional"))
      (node (ref "CON2") (pin "SH2") (pinfunction "GND_SH2") (pintype "bidirectional"))
      (node (ref "CON2") (pin "SH3") (pinfunction "GND_SH3") (pintype "bidirectional"))
      (node (ref "CON2") (pin "SH4") (pinfunction "GND_SH4") (pintype "bidirectional"))
      (node (ref "CON2") (pin "SH5") (pinfunction "GND_SH5") (pintype "bidirectional"))
      (node (ref "CON2") (pin "SH6") (pinfunction "GND_SH6") (pintype "bidirectional"))
      (node (ref "CON2") (pin "SH7") (pinfunction "GND_SH7") (pintype "bidirectional"))
      (node (ref "CON2") (pin "SH8") (pinfunction "GND_SH8") (pintype "bidirectional"))
      (node (ref "D1") (pin "A") (pinfunction "A_A") (pintype "passive"))
      (node (ref "D2") (pin "A") (pinfunction "A_A") (pintype "passive"))
      (node (ref "D3") (pin "A") (pinfunction "A_A") (pintype "passive"))
      (node (ref "D4") (pin "A") (pinfunction "A_A") (pintype "passive"))
      (node (ref "D5") (pin "A") (pinfunction "A_A") (pintype "passive"))
      (node (ref "D6") (pin "A") (pinfunction "A_A") (pintype "passive"))
      (node (ref "D7") (pin "A") (pinfunction "A_A") (pintype "passive"))
      (node (ref "D8") (pin "A") (pinfunction "A_A") (pintype "passive"))
      (node (ref "R12") (pin "1") (pinfunction "1_1") (pintype "passive"))
      (node (ref "R16") (pin "2") (pinfunction "2_2") (pintype "passive"))
      (node (ref "U11") (pin "D1") (pinfunction "GND_D1") (pintype "bidirectional"))
      (node (ref "U110") (pin "2") (pinfunction "2_2") (pintype "passive"))
      (node (ref "U30") (pin "D1") (pinfunction "PGND_D1") (pintype "bidirectional"))
      (node (ref "U30") (pin "D2") (pinfunction "PGND_D2") (pintype "bidirectional"))
      (node (ref "U30") (pin "D3") (pinfunction "PGND_D3") (pintype "bidirectional"))
      (node (ref "U30") (pin "E2") (pinfunction "DIS_E2") (pintype "bidirectional"))
      (node (ref "U4") (pin "2") (pinfunction "GND_2") (pintype "bidirectional"))
      (node (ref "U50") (pin "D3") (pinfunction "CG_D3") (pintype "bidirectional"))
      (node (ref "U6") (pin "D1") (pinfunction "GND_D1") (pintype "bidirectional"))
      (node (ref "U6") (pin "D2") (pinfunction "GND_D2") (pintype "bidirectional"))
      (node (ref "U8") (pin "2") (pinfunction "GND_2") (pintype "bidirectional"))
      (node (ref "U90") (pin "B1") (pinfunction "PGND_B1") (pintype "bidirectional"))
      (node (ref "U90") (pin "B2") (pinfunction "PT_B2") (pintype "bidirectional"))
      (node (ref "U90") (pin "C1") (pinfunction "PGND_C1") (pintype "bidirectional"))
      (node (ref "U90") (pin "C2") (pinfunction "PGND_C2") (pintype "bidirectional"))
      (node (ref "U90") (pin "C3") (pinfunction "PGND_C3") (pintype "bidirectional"))
      (node (ref "U90") (pin "C4") (pinfunction "PGND_C4") (pintype "bidirectional"))
      (node (ref "U90") (pin "D1") (pinfunction "PGND_D1") (pintype "bidirectional"))
      (node (ref "U90") (pin "D2") (pinfunction "MODE_D2") (pintype "bidirectional"))
      (node (ref "U90") (pin "E1") (pinfunction "AGND_E1") (pintype "bidirectional"))
    )
    (net (code "37") (name "GPIO31") (class "Default")
      (node (ref "BUS") (pin "31") (pinfunction "31_31") (pintype "passive"))
      (node (ref "U1") (pin "25") (pinfunction "PC5_25") (pintype "bidirectional"))
    )
    (net (code "38") (name "GPIO32") (class "Default")
      (node (ref "BUS") (pin "32") (pinfunction "32_32") (pintype "passive"))
      (node (ref "U1") (pin "24") (pinfunction "PC4_24") (pintype "passive"))
    )
    (net (code "39") (name "GPIO33") (class "Default")
      (node (ref "BUS") (pin "33") (pinfunction "33_33") (pintype "passive"))
      (node (ref "U1") (pin "23") (pinfunction "PA7_23") (pintype "power_in"))
    )
    (net (code "40") (name "GPIO34") (class "Default")
      (node (ref "BUS") (pin "34") (pinfunction "34_34") (pintype "passive"))
      (node (ref "U1") (pin "22") (pinfunction "PA6_22") (pintype "bidirectional"))
    )
    (net (code "41") (name "GPIO35") (class "Default")
      (node (ref "BUS") (pin "35") (pinfunction "35_35") (pintype "passive"))
      (node (ref "U1") (pin "21") (pinfunction "PA5_21") (pintype "bidirectional"))
    )
    (net (code "42") (name "GPIO36") (class "Default")
      (node (ref "BUS") (pin "36") (pinfunction "36_36") (pintype "passive"))
      (node (ref "U1") (pin "20") (pinfunction "PA4_20") (pintype "bidirectional"))
    )
    (net (code "43") (name "HSE_IN") (class "Default")
      (node (ref "C6") (pin "1") (pinfunction "1_1") (pintype "passive"))
      (node (ref "Q1") (pin "1") (pinfunction "1_1") (pintype "passive"))
      (node (ref "U1") (pin "5") (pinfunction "PD0_OSC_IN_5") (pintype "input"))
    )
    (net (code "44") (name "HSE_OUT") (class "Default")
      (node (ref "R2") (pin "1") (pinfunction "1_1") (pintype "passive"))
      (node (ref "U1") (pin "6") (pinfunction "PD1_OSC_OUT_6") (pintype "output"))
    )
    (net (code "45") (name "I2C_SCL") (class "Default")
      (node (ref "U11") (pin "C1") (pinfunction "SCL_C1") (pintype "bidirectional"))
    )
    (net (code "46") (name "I2C_SDA") (class "Default")
      (node (ref "U11") (pin "B1") (pinfunction "SDA_B1") (pintype "bidirectional"))
    )
    (net (code "47") (name "LED_BLUE") (class "Default")
      (node (ref "LED1") (pin "1") (pinfunction "1_1") (pintype "passive"))
      (node (ref "U11") (pin "D2") (pinfunction "OUT3_D2") (pintype "bidirectional"))
    )
    (net (code "48") (name "LED_GREEN") (class "Default")
      (node (ref "LED1") (pin "4") (pinfunction "4_4") (pintype "passive"))
      (node (ref "U11") (pin "C2") (pinfunction "OUT2_C2") (pintype "bidirectional"))
    )
    (net (code "49") (name "LED_RED") (class "Default")
      (node (ref "LED1") (pin "3") (pinfunction "3_3") (pintype "passive"))
      (node (ref "U11") (pin "B2") (pinfunction "OUT1_B2") (pintype "bidirectional"))
    )
    (net (code "50") (name "LSE_IN") (class "Default")
      (node (ref "C10") (pin "1") (pinfunction "1_1") (pintype "passive"))
      (node (ref "Q2") (pin "1") (pinfunction "1_1") (pintype "passive"))
      (node (ref "U1") (pin "3") (pinfunction "PC14-OSC32_IN_3") (pintype "input"))
    )
    (net (code "51") (name "LSE_OUT") (class "Default")
      (node (ref "R3") (pin "1") (pinfunction "1_1") (pintype "passive"))
      (node (ref "U1") (pin "4") (pinfunction "PC15-OSC32_OUT_4") (pintype "output"))
    )
    (net (code "52") (name "Net-(C11-Pad1)") (class "Default")
      (node (ref "C11") (pin "1") (pinfunction "1_1") (pintype "passive"))
      (node (ref "Q2") (pin "2") (pinfunction "2_2") (pintype "passive"))
      (node (ref "R3") (pin "2") (pinfunction "2_2") (pintype "passive"))
    )
    (net (code "53") (name "Net-(C17-Pad1)") (class "Default")
      (node (ref "C17") (pin "1") (pinfunction "1_1") (pintype "passive"))
      (node (ref "U6") (pin "A1") (pinfunction "VBUS_A1") (pintype "bidirectional"))
      (node (ref "U6") (pin "B1") (pinfunction "VBUS_B1") (pintype "bidirectional"))
      (node (ref "U6") (pin "C1") (pinfunction "VBUS_C1") (pintype "bidirectional"))
    )
    (net (code "54") (name "Net-(C31-Pad1)") (class "Default")
      (node (ref "C31") (pin "1") (pinfunction "1_1") (pintype "passive"))
      (node (ref "U30") (pin "B1") (pinfunction "PMID_B1") (pintype "bidirectional"))
      (node (ref "U30") (pin "B2") (pinfunction "PMID_B2") (pintype "bidirectional"))
      (node (ref "U30") (pin "B3") (pinfunction "PMID_B3") (pintype "bidirectional"))
    )
    (net (code "55") (name "Net-(CON2-VCC)") (class "Default")
      (node (ref "CON2") (pin "1") (pinfunction "VCC_1") (pintype "bidirectional"))
      (node (ref "F1") (pin "1") (pinfunction "1_1") (pintype "passive"))
    )
    (net (code "56") (name "Net-(L30-Pad1)") (class "Default")
      (node (ref "L30") (pin "1") (pinfunction "1_1") (pintype "passive"))
      (node (ref "U30") (pin "C1") (pinfunction "SW_C1") (pintype "bidirectional"))
      (node (ref "U30") (pin "C2") (pinfunction "SW_C2") (pintype "bidirectional"))
      (node (ref "U30") (pin "C3") (pinfunction "SW_C3") (pintype "bidirectional"))
    )
    (net (code "57") (name "Net-(L90-Pad1)") (class "Default")
      (node (ref "L90") (pin "1") (pinfunction "1_1") (pintype "passive"))
      (node (ref "U90") (pin "B3") (pinfunction "SW1_B3") (pintype "bidirectional"))
      (node (ref "U90") (pin "B4") (pinfunction "SW1_B4") (pintype "bidirectional"))
    )
    (net (code "58") (name "Net-(L90-Pad2)") (class "Default")
      (node (ref "L90") (pin "2") (pinfunction "2_2") (pintype "passive"))
      (node (ref "U90") (pin "D3") (pinfunction "SW2_D3") (pintype "bidirectional"))
      (node (ref "U90") (pin "D4") (pinfunction "SW2_D4") (pintype "bidirectional"))
    )
    (net (code "59") (name "Net-(Q1-2)") (class "Default")
      (node (ref "C9") (pin "1") (pinfunction "1_1") (pintype "passive"))
      (node (ref "Q1") (pin "3") (pinfunction "2_3") (pintype "passive"))
      (node (ref "R2") (pin "2") (pinfunction "2_2") (pintype "passive"))
    )
    (net (code "60") (name "Net-(U1-VBAT)") (class "Default")
      (node (ref "R1") (pin "2") (pinfunction "2_2") (pintype "passive"))
      (node (ref "U1") (pin "1") (pinfunction "VBAT_1") (pintype "input"))
    )
    (net (code "61") (name "Net-(U6-VOUT-PadA2)") (class "Default")
      (node (ref "U6") (pin "A2") (pinfunction "VOUT_A2") (pintype "bidirectional"))
      (node (ref "U6") (pin "A3") (pinfunction "VOUT_A3") (pintype "bidirectional"))
      (node (ref "U6") (pin "B3") (pinfunction "VOUT_B3") (pintype "bidirectional"))
      (node (ref "U6") (pin "C3") (pinfunction "VOUT_C3") (pintype "bidirectional"))
    )
    (net (code "62") (name "Net-(U30-VREG)") (class "Default")
      (node (ref "C34") (pin "1") (pinfunction "1_1") (pintype "passive"))
      (node (ref "U30") (pin "E3") (pinfunction "VREG_E3") (pintype "bidirectional"))
    )
    (net (code "63") (name "Net-(U40-VDD)") (class "Default")
      (node (ref "C41") (pin "1") (pinfunction "1_1") (pintype "passive"))
      (node (ref "R40") (pin "1") (pinfunction "1_1") (pintype "passive"))
      (node (ref "U40") (pin "3") (pinfunction "VDD_3") (pintype "power_in"))
    )
    (net (code "64") (name "Net-(U40-VM)") (class "Default")
      (node (ref "R41") (pin "2") (pinfunction "2_2") (pintype "passive"))
      (node (ref "U40") (pin "5") (pinfunction "VM_5") (pintype "input"))
    )
    (net (code "65") (name "Net-(U50-VIN)") (class "Default")
      (node (ref "C19") (pin "1") (pinfunction "1_1") (pintype "passive"))
      (node (ref "R17") (pin "2") (pinfunction "2_2") (pintype "passive"))
      (node (ref "U50") (pin "A3") (pinfunction "VIN_A3") (pintype "bidirectional"))
    )
    (net (code "66") (name "Net-(U90-EN)") (class "Default")
      (node (ref "R11") (pin "1") (pinfunction "1_1") (pintype "passive"))
      (node (ref "R12") (pin "2") (pinfunction "2_2") (pintype "passive"))
      (node (ref "U90") (pin "A2") (pinfunction "EN_A2") (pintype "bidirectional"))
    )
    (net (code "67") (name "SDC_CD") (class "Default")
      (node (ref "D8") (pin "C") (pinfunction "C_C") (pintype "passive"))
      (node (ref "R9") (pin "1") (pinfunction "1_1") (pintype "passive"))
    )
    (net (code "68") (name "SDC_CLK") (class "Default")
      (node (ref "CON1") (pin "P$5") (pinfunction "CLK_P$5") (pintype "bidirectional"))
      (node (ref "D5") (pin "C") (pinfunction "C_C") (pintype "passive"))
      (node (ref "U1") (pin "55") (pinfunction "PB3_55") (pintype "bidirectional"))
    )
    (net (code "69") (name "SDC_CS") (class "Default")
      (node (ref "CON1") (pin "P$2") (pinfunction "CD/DAT3_P$2") (pintype "input"))
      (node (ref "D2") (pin "C") (pinfunction "C_C") (pintype "passive"))
      (node (ref "R5") (pin "1") (pinfunction "1_1") (pintype "passive"))
      (node (ref "U1") (pin "50") (pinfunction "PA15_50") (pintype "bidirectional"))
    )
    (net (code "70") (name "SDC_DAT1") (class "Default")
      (node (ref "D7") (pin "C") (pinfunction "C_C") (pintype "passive"))
      (node (ref "R8") (pin "1") (pinfunction "1_1") (pintype "passive"))
    )
    (net (code "71") (name "SDC_DAT2") (class "Default")
      (node (ref "D1") (pin "C") (pinfunction "C_C") (pintype "passive"))
      (node (ref "R4") (pin "1") (pinfunction "1_1") (pintype "passive"))
    )
    (net (code "72") (name "SDC_DET") (class "Default")
      (node (ref "CON1") (pin "P$13") (pinfunction "CD_P$13") (pintype "power_in"))
    )
    (net (code "73") (name "SDC_MISO") (class "Default")
      (node (ref "CON1") (pin "P$7") (pinfunction "DAT0_P$7") (pintype "power_in"))
      (node (ref "D6") (pin "C") (pinfunction "C_C") (pintype "passive"))
      (node (ref "R7") (pin "1") (pinfunction "1_1") (pintype "passive"))
      (node (ref "U1") (pin "56") (pinfunction "PB4_56") (pintype "bidirectional"))
    )
    (net (code "74") (name "SDC_MOSI") (class "Default")
      (node (ref "CON1") (pin "P$3") (pinfunction "CMD_P$3") (pintype "input"))
      (node (ref "D3") (pin "C") (pinfunction "C_C") (pintype "passive"))
      (node (ref "R6") (pin "1") (pinfunction "1_1") (pintype "passive"))
      (node (ref "U1") (pin "57") (pinfunction "PB5_57") (pintype "bidirectional"))
    )
    (net (code "75") (name "SDC_VDD") (class "Default")
      (node (ref "C12") (pin "1") (pinfunction "1_1") (pintype "passive"))
      (node (ref "CON1") (pin "P$4") (pinfunction "VDD_P$4") (pintype "input"))
      (node (ref "D4") (pin "C") (pinfunction "C_C") (pintype "passive"))
      (node (ref "R4") (pin "2") (pinfunction "2_2") (pintype "passive"))
      (node (ref "R5") (pin "2") (pinfunction "2_2") (pintype "passive"))
      (node (ref "R6") (pin "2") (pinfunction "2_2") (pintype "passive"))
      (node (ref "R7") (pin "2") (pinfunction "2_2") (pintype "passive"))
      (node (ref "R8") (pin "2") (pinfunction "2_2") (pintype "passive"))
      (node (ref "R9") (pin "2") (pinfunction "2_2") (pintype "passive"))
    )
    (net (code "76") (name "SW") (class "Default")
      (node (ref "C32") (pin "1") (pinfunction "1_1") (pintype "passive"))
      (node (ref "L30") (pin "2") (pinfunction "2_2") (pintype "passive"))
      (node (ref "R30") (pin "1") (pinfunction "1_1") (pintype "passive"))
      (node (ref "U30") (pin "E1") (pinfunction "CSIN_E1") (pintype "bidirectional"))
    )
    (net (code "77") (name "USB_DM") (class "Default")
      (node (ref "U1") (pin "44") (pinfunction "PA11_44") (pintype "bidirectional"))
      (node (ref "U8") (pin "6") (pinfunction "IO1_6") (pintype "bidirectional"))
    )
    (net (code "78") (name "USB_DM_RAW") (class "Default")
      (node (ref "CON2") (pin "2") (pinfunction "DM_2") (pintype "bidirectional"))
      (node (ref "U8") (pin "1") (pinfunction "IO1_1") (pintype "bidirectional"))
    )
    (net (code "79") (name "USB_DP") (class "Default")
      (node (ref "U1") (pin "45") (pinfunction "PA12_45") (pintype "bidirectional"))
      (node (ref "U8") (pin "4") (pinfunction "IO2_4") (pintype "bidirectional"))
    )
    (net (code "80") (name "USB_DP_RAW") (class "Default")
      (node (ref "CON2") (pin "3") (pinfunction "DP_3") (pintype "bidirectional"))
      (node (ref "U8") (pin "3") (pinfunction "IO2_3") (pintype "bidirectional"))
    )
    (net (code "81") (name "USB_FS_ID") (class "Default")
      (node (ref "U1") (pin "43") (pinfunction "PA10_43") (pintype "bidirectional"))
    )
    (net (code "82") (name "USB_ID") (class "Default")
      (node (ref "CON2") (pin "4") (pinfunction "ID_4") (pintype "bidirectional"))
    )
    (net (code "83") (name "USB_VBUS") (class "Default")
      (node (ref "U1") (pin "42") (pinfunction "PA9_42") (pintype "bidirectional"))
    )
    (net (code "84") (name "VBAT_PLUS") (class "Default")
      (node (ref "C33") (pin "1") (pinfunction "1_1") (pintype "passive"))
      (node (ref "C92") (pin "1") (pinfunction "1_1") (pintype "passive"))
      (node (ref "R11") (pin "2") (pinfunction "2_2") (pintype "passive"))
      (node (ref "R30") (pin "2") (pinfunction "2_2") (pintype "passive"))
      (node (ref "U30") (pin "E4") (pinfunction "VBAT_E4") (pintype "bidirectional"))
      (node (ref "U90") (pin "A1") (pinfunction "AVIN_A1") (pintype "bidirectional"))
      (node (ref "U90") (pin "A3") (pinfunction "PVIN_A3") (pintype "bidirectional"))
      (node (ref "U90") (pin "A4") (pinfunction "PVIN_A4") (pintype "bidirectional"))
    )
    (net (code "85") (name "VBUS_USB") (class "Default")
      (node (ref "C13") (pin "1") (pinfunction "1_1") (pintype "passive"))
      (node (ref "C14") (pin "1") (pinfunction "1_1") (pintype "passive"))
      (node (ref "F1") (pin "2") (pinfunction "2_2") (pintype "passive"))
      (node (ref "U4") (pin "1") (pinfunction "VOUT_1") (pintype "bidirectional"))
      (node (ref "U8") (pin "5") (pinfunction "VBUS_5") (pintype "bidirectional"))
    )
    (net (code "86") (name "VCC") (class "Default")
      (node (ref "LED1") (pin "2") (pinfunction "2_2") (pintype "passive"))
      (node (ref "U11") (pin "A2") (pinfunction "VCC_A2") (pintype "bidirectional"))
      (node (ref "U110") (pin "1") (pinfunction "1_1") (pintype "passive"))
    )
    (net (code "87") (name "VDD") (class "Default")
      (node (ref "C2") (pin "1") (pinfunction "1_1") (pintype "passive"))
      (node (ref "C3") (pin "1") (pinfunction "1_1") (pintype "passive"))
      (node (ref "C4") (pin "1") (pinfunction "1_1") (pintype "passive"))
      (node (ref "C5") (pin "1") (pinfunction "1_1") (pintype "passive"))
      (node (ref "C8") (pin "1") (pinfunction "1_1") (pintype "passive"))
      (node (ref "U1") (pin "19") (pinfunction "VDD_4_19") (pintype "power_in"))
      (node (ref "U1") (pin "32") (pinfunction "VDD_1_32") (pintype "power_in"))
      (node (ref "U1") (pin "48") (pinfunction "VDD_2_48") (pintype "power_in"))
      (node (ref "U1") (pin "64") (pinfunction "VDD_3_64") (pintype "power_in"))
    )
    (net (code "88") (name "VDDA") (class "Default")
      (node (ref "C1") (pin "1") (pinfunction "1_1") (pintype "passive"))
      (node (ref "C7") (pin "1") (pinfunction "1_1") (pintype "passive"))
      (node (ref "U1") (pin "13") (pinfunction "VDDA_13") (pintype "power_in"))
    )
    (net (code "89") (name "VIN_PS") (class "Default")
      (node (ref "C15") (pin "1") (pinfunction "1_1") (pintype "passive"))
      (node (ref "C30") (pin "1") (pinfunction "1_1") (pintype "passive"))
      (node (ref "U30") (pin "A1") (pinfunction "VBUS_A1") (pintype "bidirectional"))
      (node (ref "U30") (pin "A2") (pinfunction "VBUS_A2") (pintype "bidirectional"))
      (node (ref "U4") (pin "5") (pinfunction "VIN_5") (pintype "bidirectional"))
    )
    (net (code "90") (name "VSYS") (class "Default")
      (node (ref "C90") (pin "1") (pinfunction "1_1") (pintype "passive"))
      (node (ref "C91") (pin "1") (pinfunction "1_1") (pintype "passive"))
      (node (ref "U90") (pin "E3") (pinfunction "VOUT_E3") (pintype "bidirectional"))
      (node (ref "U90") (pin "E4") (pinfunction "VOUT_E4") (pintype "bidirectional"))
    )
    (net (code "91") (name "unconnected-(BUS-Pad5)") (class "Default")
      (node (ref "BUS") (pin "5") (pinfunction "5_5") (pintype "passive"))
    )
    (net (code "92") (name "unconnected-(BUS-Pad6)") (class "Default")
      (node (ref "BUS") (pin "6") (pinfunction "6_6") (pintype "passive"))
    )
    (net (code "93") (name "unconnected-(CON1-DAT2-PadP$1)") (class "Default")
      (node (ref "CON1") (pin "P$1") (pinfunction "DAT2_P$1") (pintype "output"))
    )
    (net (code "94") (name "unconnected-(R1-Pad1)") (class "Default")
      (node (ref "R1") (pin "1") (pinfunction "1_1") (pintype "passive"))
    )
    (net (code "95") (name "unconnected-(R10-Pad1)") (class "Default")
      (node (ref "R10") (pin "1") (pinfunction "1_1") (pintype "passive"))
    )
    (net (code "96") (name "unconnected-(R10-Pad2)") (class "Default")
      (node (ref "R10") (pin "2") (pinfunction "2_2") (pintype "passive"))
    )
    (net (code "97") (name "unconnected-(S1-Pad1)") (class "Default")
      (node (ref "S1") (pin "1") (pinfunction "1_1") (pintype "passive"))
    )
    (net (code "98") (name "unconnected-(S1-Pad2)") (class "Default")
      (node (ref "S1") (pin "2") (pinfunction "2_2") (pintype "passive"))
    )
    (net (code "99") (name "unconnected-(S1-Pad3)") (class "Default")
      (node (ref "S1") (pin "3") (pinfunction "3_3") (pintype "passive"))
    )
    (net (code "100") (name "unconnected-(S1-Pad4)") (class "Default")
      (node (ref "S1") (pin "4") (pinfunction "4_4") (pintype "passive"))
    )
    (net (code "101") (name "unconnected-(S1-SHIELD-Pad5)") (class "Default")
      (node (ref "S1") (pin "5") (pinfunction "SHIELD_5") (pintype "passive"))
    )
    (net (code "102") (name "unconnected-(S2-2-Pad3)") (class "Default")
      (node (ref "S2") (pin "3") (pinfunction "2_3") (pintype "bidirectional"))
    )
    (net (code "103") (name "unconnected-(S2-C-Pad4)") (class "Default")
      (node (ref "S2") (pin "4") (pinfunction "C_4") (pintype "bidirectional"))
    )
    (net (code "104") (name "unconnected-(S2-G-Pad5)") (class "Default")
      (node (ref "S2") (pin "5") (pinfunction "G_5") (pintype "bidirectional"))
    )
    (net (code "105") (name "unconnected-(S2-Pad1)") (class "Default")
      (node (ref "S2") (pin "1") (pinfunction "1_1") (pintype "bidirectional"))
    )
    (net (code "106") (name "unconnected-(S2-T-Pad2)") (class "Default")
      (node (ref "S2") (pin "2") (pinfunction "T_2") (pintype "bidirectional"))
    )
    (net (code "107") (name "unconnected-(U1-BOOT0-Pad60)") (class "Default")
      (node (ref "U1") (pin "60") (pinfunction "BOOT0_60") (pintype "passive"))
    )
    (net (code "108") (name "unconnected-(U1-PA0-WKUP-Pad14)") (class "Default")
      (node (ref "U1") (pin "14") (pinfunction "PA0-WKUP_14") (pintype "bidirectional"))
    )
    (net (code "109") (name "unconnected-(U1-PA1-Pad15)") (class "Default")
      (node (ref "U1") (pin "15") (pinfunction "PA1_15") (pintype "bidirectional"))
    )
    (net (code "110") (name "unconnected-(U1-PB0-Pad26)") (class "Default")
      (node (ref "U1") (pin "26") (pinfunction "PB0_26") (pintype "bidirectional"))
    )
    (net (code "111") (name "unconnected-(U1-PB1-Pad27)") (class "Default")
      (node (ref "U1") (pin "27") (pinfunction "PB1_27") (pintype "bidirectional"))
    )
    (net (code "112") (name "unconnected-(U1-PC0-Pad8)") (class "Default")
      (node (ref "U1") (pin "8") (pinfunction "PC0_8") (pintype "bidirectional"))
    )
    (net (code "113") (name "unconnected-(U1-PC1-Pad9)") (class "Default")
      (node (ref "U1") (pin "9") (pinfunction "PC1_9") (pintype "bidirectional"))
    )
    (net (code "114") (name "unconnected-(U1-PC2-Pad10)") (class "Default")
      (node (ref "U1") (pin "10") (pinfunction "PC2_10") (pintype "bidirectional"))
    )
    (net (code "115") (name "unconnected-(U1-PC3-Pad11)") (class "Default")
      (node (ref "U1") (pin "11") (pinfunction "PC3_11") (pintype "bidirectional"))
    )
    (net (code "116") (name "unconnected-(U1-PC13-TAMPER-RTC-Pad2)") (class "Default")
      (node (ref "U1") (pin "2") (pinfunction "PC13-TAMPER-RTC_2") (pintype "input"))
    )
    (net (code "117") (name "unconnected-(U1-PD2-Pad54)") (class "Default")
      (node (ref "U1") (pin "54") (pinfunction "PD2_54") (pintype "bidirectional"))
    )
    (net (code "118") (name "unconnected-(U1-VSSA-Pad12)") (class "Default")
      (node (ref "U1") (pin "12") (pinfunction "VSSA_12") (pintype "passive"))
    )
    (net (code "119") (name "unconnected-(U1-VSS_1-Pad31)") (class "Default")
      (node (ref "U1") (pin "31") (pinfunction "VSS_1_31") (pintype "passive"))
    )
    (net (code "120") (name "unconnected-(U1-VSS_2-Pad47)") (class "Default")
      (node (ref "U1") (pin "47") (pinfunction "VSS_2_47") (pintype "passive"))
    )
    (net (code "121") (name "unconnected-(U1-VSS_3-Pad63)") (class "Default")
      (node (ref "U1") (pin "63") (pinfunction "VSS_3_63") (pintype "passive"))
    )
    (net (code "122") (name "unconnected-(U1-VSS_4-Pad18)") (class "Default")
      (node (ref "U1") (pin "18") (pinfunction "VSS_4_18") (pintype "passive"))
    )
    (net (code "123") (name "unconnected-(U4-EN-Pad4)") (class "Default")
      (node (ref "U4") (pin "4") (pinfunction "EN_4") (pintype "bidirectional"))
    )
    (net (code "124") (name "unconnected-(U4-FLG-Pad3)") (class "Default")
      (node (ref "U4") (pin "3") (pinfunction "FLG_3") (pintype "bidirectional"))
    )
    (net (code "125") (name "unconnected-(U6-AVA-PadB2)") (class "Default")
      (node (ref "U6") (pin "B2") (pinfunction "AVA_B2") (pintype "bidirectional"))
    )
    (net (code "126") (name "unconnected-(U6-DF_IN-PadD3)") (class "Default")
      (node (ref "U6") (pin "D3") (pinfunction "DF_IN_D3") (pintype "bidirectional"))
    )
    (net (code "127") (name "unconnected-(U6-EN-PadC2)") (class "Default")
      (node (ref "U6") (pin "C2") (pinfunction "EN_C2") (pintype "bidirectional"))
    )
    (net (code "128") (name "unconnected-(U6-SEL-PadD4)") (class "Default")
      (node (ref "U6") (pin "D4") (pinfunction "SEL_D4") (pintype "bidirectional"))
    )
    (net (code "129") (name "unconnected-(U11-SDB-PadA1)") (class "Default")
      (node (ref "U11") (pin "A1") (pinfunction "SDB_A1") (pintype "bidirectional"))
    )
    (net (code "130") (name "unconnected-(U20-CANH-Pad7)") (class "Default")
      (node (ref "U20") (pin "7") (pinfunction "CANH_7") (pintype "bidirectional"))
    )
    (net (code "131") (name "unconnected-(U20-CANL-Pad6)") (class "Default")
      (node (ref "U20") (pin "6") (pinfunction "CANL_6") (pintype "bidirectional"))
    )
    (net (code "132") (name "unconnected-(U20-RS-Pad8)") (class "Default")
      (node (ref "U20") (pin "8") (pinfunction "RS_8") (pintype "bidirectional"))
    )
    (net (code "133") (name "unconnected-(U20-RXD-Pad4)") (class "Default")
      (node (ref "U20") (pin "4") (pinfunction "RXD_4") (pintype "bidirectional"))
    )
    (net (code "134") (name "unconnected-(U20-TXD-Pad1)") (class "Default")
      (node (ref "U20") (pin "1") (pinfunction "TXD_1") (pintype "bidirectional"))
    )
    (net (code "135") (name "unconnected-(U20-VDD-Pad3)") (class "Default")
      (node (ref "U20") (pin "3") (pinfunction "VDD_3") (pintype "bidirectional"))
    )
    (net (code "136") (name "unconnected-(U20-VREF-Pad5)") (class "Default")
      (node (ref "U20") (pin "5") (pinfunction "VREF_5") (pintype "bidirectional"))
    )
    (net (code "137") (name "unconnected-(U20-VSS-Pad2)") (class "Default")
      (node (ref "U20") (pin "2") (pinfunction "VSS_2") (pintype "bidirectional"))
    )
    (net (code "138") (name "unconnected-(U30-NC-PadA3)") (class "Default")
      (node (ref "U30") (pin "A3") (pinfunction "NC_A3") (pintype "no_connect"))
    )
    (net (code "139") (name "unconnected-(U30-OTG-PadD4)") (class "Default")
      (node (ref "U30") (pin "D4") (pinfunction "OTG_D4") (pintype "bidirectional"))
    )
    (net (code "140") (name "unconnected-(U30-STAT-PadC4)") (class "Default")
      (node (ref "U30") (pin "C4") (pinfunction "STAT_C4") (pintype "bidirectional"))
    )
    (net (code "141") (name "unconnected-(U50-ALM-PadA1)") (class "Default")
      (node (ref "U50") (pin "A1") (pinfunction "ALM_A1") (pintype "bidirectional"))
    )
    (net (code "142") (name "unconnected-(U50-RSTIO-PadC3)") (class "Default")
      (node (ref "U50") (pin "C3") (pinfunction "RSTIO_C3") (pintype "bidirectional"))
    )
    (net (code "143") (name "unconnected-(U90-PG-PadE2)") (class "Default")
      (node (ref "U90") (pin "E2") (pinfunction "PG_E2") (pintype "bidirectional"))
    )
  )
)
